# Impedance_Analyzer.net
KiCad netlist of a schematic drawn in EAGLE
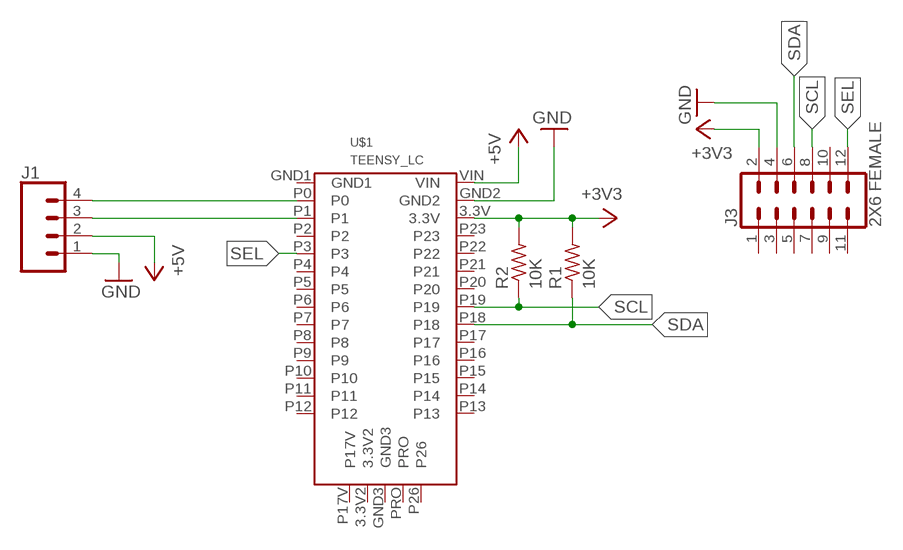
[diagram p0: schematic, sheet 1]

(export (version "E")
  (design (tool "Eeschema 10.0.6"))
  (components
    (comp (ref "J1")
      (value "CONN_04")
      (footprint "eagle-import:1X04")
      (libsource (lib "eagle-import") (part "CONN_04"))
    )
    (comp (ref "J3")
      (value "2X6 FEMALE")
      (footprint "eagle-import:2X6")
      (libsource (lib "eagle-import") (part "CONN_06X2PTH_FEMALE"))
    )
    (comp (ref "R1")
      (value "10K")
      (footprint "eagle-import:0204_5")
      (libsource (lib "eagle-import") (part "R-US_0204/5"))
    )
    (comp (ref "R2")
      (value "10K")
      (footprint "eagle-import:0204_5")
      (libsource (lib "eagle-import") (part "R-US_0204/5"))
    )
    (comp (ref "U$1")
      (value "TEENSY_LC")
      (footprint "eagle-import:TEENSY_LC")
      (libsource (lib "eagle-import") (part "TEENSY_LC"))
    )
  )
  (nets
    (net (code "1") (name "+3V3") (class "Default")
      (node (ref "J3") (pin "2") (pinfunction "2_2") (pintype "passive"))
      (node (ref "R1") (pin "2") (pinfunction "2_2") (pintype "passive"))
      (node (ref "R2") (pin "2") (pinfunction "2_2") (pintype "passive"))
      (node (ref "U$1") (pin "3.3V") (pinfunction "3.3V_3.3V") (pintype "bidirectional"))
    )
    (net (code "2") (name "+5V") (class "Default")
      (node (ref "J1") (pin "2") (pinfunction "2_2") (pintype "passive"))
      (node (ref "U$1") (pin "VIN") (pinfunction "VIN_VIN") (pintype "bidirectional"))
    )
    (net (code "3") (name "GND") (class "Default")
      (node (ref "J1") (pin "1") (pinfunction "1_1") (pintype "passive"))
      (node (ref "J3") (pin "4") (pinfunction "4_4") (pintype "passive"))
      (node (ref "U$1") (pin "GND2") (pinfunction "GND2_GND2") (pintype "bidirectional"))
    )
    (net (code "4") (name "Net-(J1-Pad3)") (class "Default")
      (node (ref "J1") (pin "3") (pinfunction "3_3") (pintype "passive"))
      (node (ref "U$1") (pin "P1") (pinfunction "P1_P1") (pintype "bidirectional"))
    )
    (net (code "5") (name "Net-(J1-Pad4)") (class "Default")
      (node (ref "J1") (pin "4") (pinfunction "4_4") (pintype "passive"))
      (node (ref "U$1") (pin "P0") (pinfunction "P0_P0") (pintype "bidirectional"))
    )
    (net (code "6") (name "SCL") (class "Default")
      (node (ref "J3") (pin "8") (pinfunction "8_8") (pintype "passive"))
      (node (ref "R2") (pin "1") (pinfunction "1_1") (pintype "passive"))
      (node (ref "U$1") (pin "P19") (pinfunction "P19_P19") (pintype "bidirectional"))
    )
    (net (code "7") (name "SDA") (class "Default")
      (node (ref "J3") (pin "6") (pinfunction "6_6") (pintype "passive"))
      (node (ref "R1") (pin "1") (pinfunction "1_1") (pintype "passive"))
      (node (ref "U$1") (pin "P18") (pinfunction "P18_P18") (pintype "bidirectional"))
    )
    (net (code "8") (name "SEL") (class "Default")
      (node (ref "J3") (pin "12") (pinfunction "12_12") (pintype "passive"))
      (node (ref "U$1") (pin "P3") (pinfunction "P3_P3") (pintype "bidirectional"))
    )
    (net (code "9") (name "unconnected-(J3-Pad1)") (class "Default")
      (node (ref "J3") (pin "1") (pinfunction "1_1") (pintype "passive"))
    )
    (net (code "10") (name "unconnected-(J3-Pad3)") (class "Default")
      (node (ref "J3") (pin "3") (pinfunction "3_3") (pintype "passive"))
    )
    (net (code "11") (name "unconnected-(J3-Pad5)") (class "Default")
      (node (ref "J3") (pin "5") (pinfunction "5_5") (pintype "passive"))
    )
    (net (code "12") (name "unconnected-(J3-Pad7)") (class "Default")
      (node (ref "J3") (pin "7") (pinfunction "7_7") (pintype "passive"))
    )
    (net (code "13") (name "unconnected-(J3-Pad9)") (class "Default")
      (node (ref "J3") (pin "9") (pinfunction "9_9") (pintype "passive"))
    )
    (net (code "14") (name "unconnected-(J3-Pad10)") (class "Default")
      (node (ref "J3") (pin "10") (pinfunction "10_10") (pintype "passive"))
    )
    (net (code "15") (name "unconnected-(J3-Pad11)") (class "Default")
      (node (ref "J3") (pin "11") (pinfunction "11_11") (pintype "passive"))
    )
    (net (code "16") (name "unconnected-(U$1-Pad3.3V2)") (class "Default")
      (node (ref "U$1") (pin "3.3V2") (pinfunction "3.3V2_3.3V2") (pintype "bidirectional"))
    )
    (net (code "17") (name "unconnected-(U$1-PadGND1)") (class "Default")
      (node (ref "U$1") (pin "GND1") (pinfunction "GND1_GND1") (pintype "bidirectional"))
    )
    (net (code "18") (name "unconnected-(U$1-PadGND3)") (class "Default")
      (node (ref "U$1") (pin "GND3") (pinfunction "GND3_GND3") (pintype "bidirectional"))
    )
    (net (code "19") (name "unconnected-(U$1-PadP2)") (class "Default")
      (node (ref "U$1") (pin "P2") (pinfunction "P2_P2") (pintype "bidirectional"))
    )
    (net (code "20") (name "unconnected-(U$1-PadP4)") (class "Default")
      (node (ref "U$1") (pin "P4") (pinfunction "P4_P4") (pintype "bidirectional"))
    )
    (net (code "21") (name "unconnected-(U$1-PadP5)") (class "Default")
      (node (ref "U$1") (pin "P5") (pinfunction "P5_P5") (pintype "bidirectional"))
    )
    (net (code "22") (name "unconnected-(U$1-PadP6)") (class "Default")
      (node (ref "U$1") (pin "P6") (pinfunction "P6_P6") (pintype "bidirectional"))
    )
    (net (code "23") (name "unconnected-(U$1-PadP7)") (class "Default")
      (node (ref "U$1") (pin "P7") (pinfunction "P7_P7") (pintype "bidirectional"))
    )
    (net (code "24") (name "unconnected-(U$1-PadP8)") (class "Default")
      (node (ref "U$1") (pin "P8") (pinfunction "P8_P8") (pintype "bidirectional"))
    )
    (net (code "25") (name "unconnected-(U$1-PadP9)") (class "Default")
      (node (ref "U$1") (pin "P9") (pinfunction "P9_P9") (pintype "bidirectional"))
    )
    (net (code "26") (name "unconnected-(U$1-PadP10)") (class "Default")
      (node (ref "U$1") (pin "P10") (pinfunction "P10_P10") (pintype "bidirectional"))
    )
    (net (code "27") (name "unconnected-(U$1-PadP11)") (class "Default")
      (node (ref "U$1") (pin "P11") (pinfunction "P11_P11") (pintype "bidirectional"))
    )
    (net (code "28") (name "unconnected-(U$1-PadP12)") (class "Default")
      (node (ref "U$1") (pin "P12") (pinfunction "P12_P12") (pintype "bidirectional"))
    )
    (net (code "29") (name "unconnected-(U$1-PadP13)") (class "Default")
      (node (ref "U$1") (pin "P13") (pinfunction "P13_P13") (pintype "bidirectional"))
    )
    (net (code "30") (name "unconnected-(U$1-PadP14)") (class "Default")
      (node (ref "U$1") (pin "P14") (pinfunction "P14_P14") (pintype "bidirectional"))
    )
    (net (code "31") (name "unconnected-(U$1-PadP15)") (class "Default")
      (node (ref "U$1") (pin "P15") (pinfunction "P15_P15") (pintype "bidirectional"))
    )
    (net (code "32") (name "unconnected-(U$1-PadP16)") (class "Default")
      (node (ref "U$1") (pin "P16") (pinfunction "P16_P16") (pintype "bidirectional"))
    )
    (net (code "33") (name "unconnected-(U$1-PadP17)") (class "Default")
      (node (ref "U$1") (pin "P17") (pinfunction "P17_P17") (pintype "bidirectional"))
    )
    (net (code "34") (name "unconnected-(U$1-PadP17V)") (class "Default")
      (node (ref "U$1") (pin "P17V") (pinfunction "P17V_P17V") (pintype "bidirectional"))
    )
    (net (code "35") (name "unconnected-(U$1-PadP20)") (class "Default")
      (node (ref "U$1") (pin "P20") (pinfunction "P20_P20") (pintype "bidirectional"))
    )
    (net (code "36") (name "unconnected-(U$1-PadP21)") (class "Default")
      (node (ref "U$1") (pin "P21") (pinfunction "P21_P21") (pintype "bidirectional"))
    )
    (net (code "37") (name "unconnected-(U$1-PadP22)") (class "Default")
      (node (ref "U$1") (pin "P22") (pinfunction "P22_P22") (pintype "bidirectional"))
    )
    (net (code "38") (name "unconnected-(U$1-PadP23)") (class "Default")
      (node (ref "U$1") (pin "P23") (pinfunction "P23_P23") (pintype "bidirectional"))
    )
    (net (code "39") (name "unconnected-(U$1-PadP26)") (class "Default")
      (node (ref "U$1") (pin "P26") (pinfunction "P26_P26") (pintype "bidirectional"))
    )
    (net (code "40") (name "unconnected-(U$1-PadPRO)") (class "Default")
      (node (ref "U$1") (pin "PRO") (pinfunction "PRO_PRO") (pintype "bidirectional"))
    )
  )
)
